# joystick-tester-smd.net
KiCad netlist of a schematic drawn in EAGLE
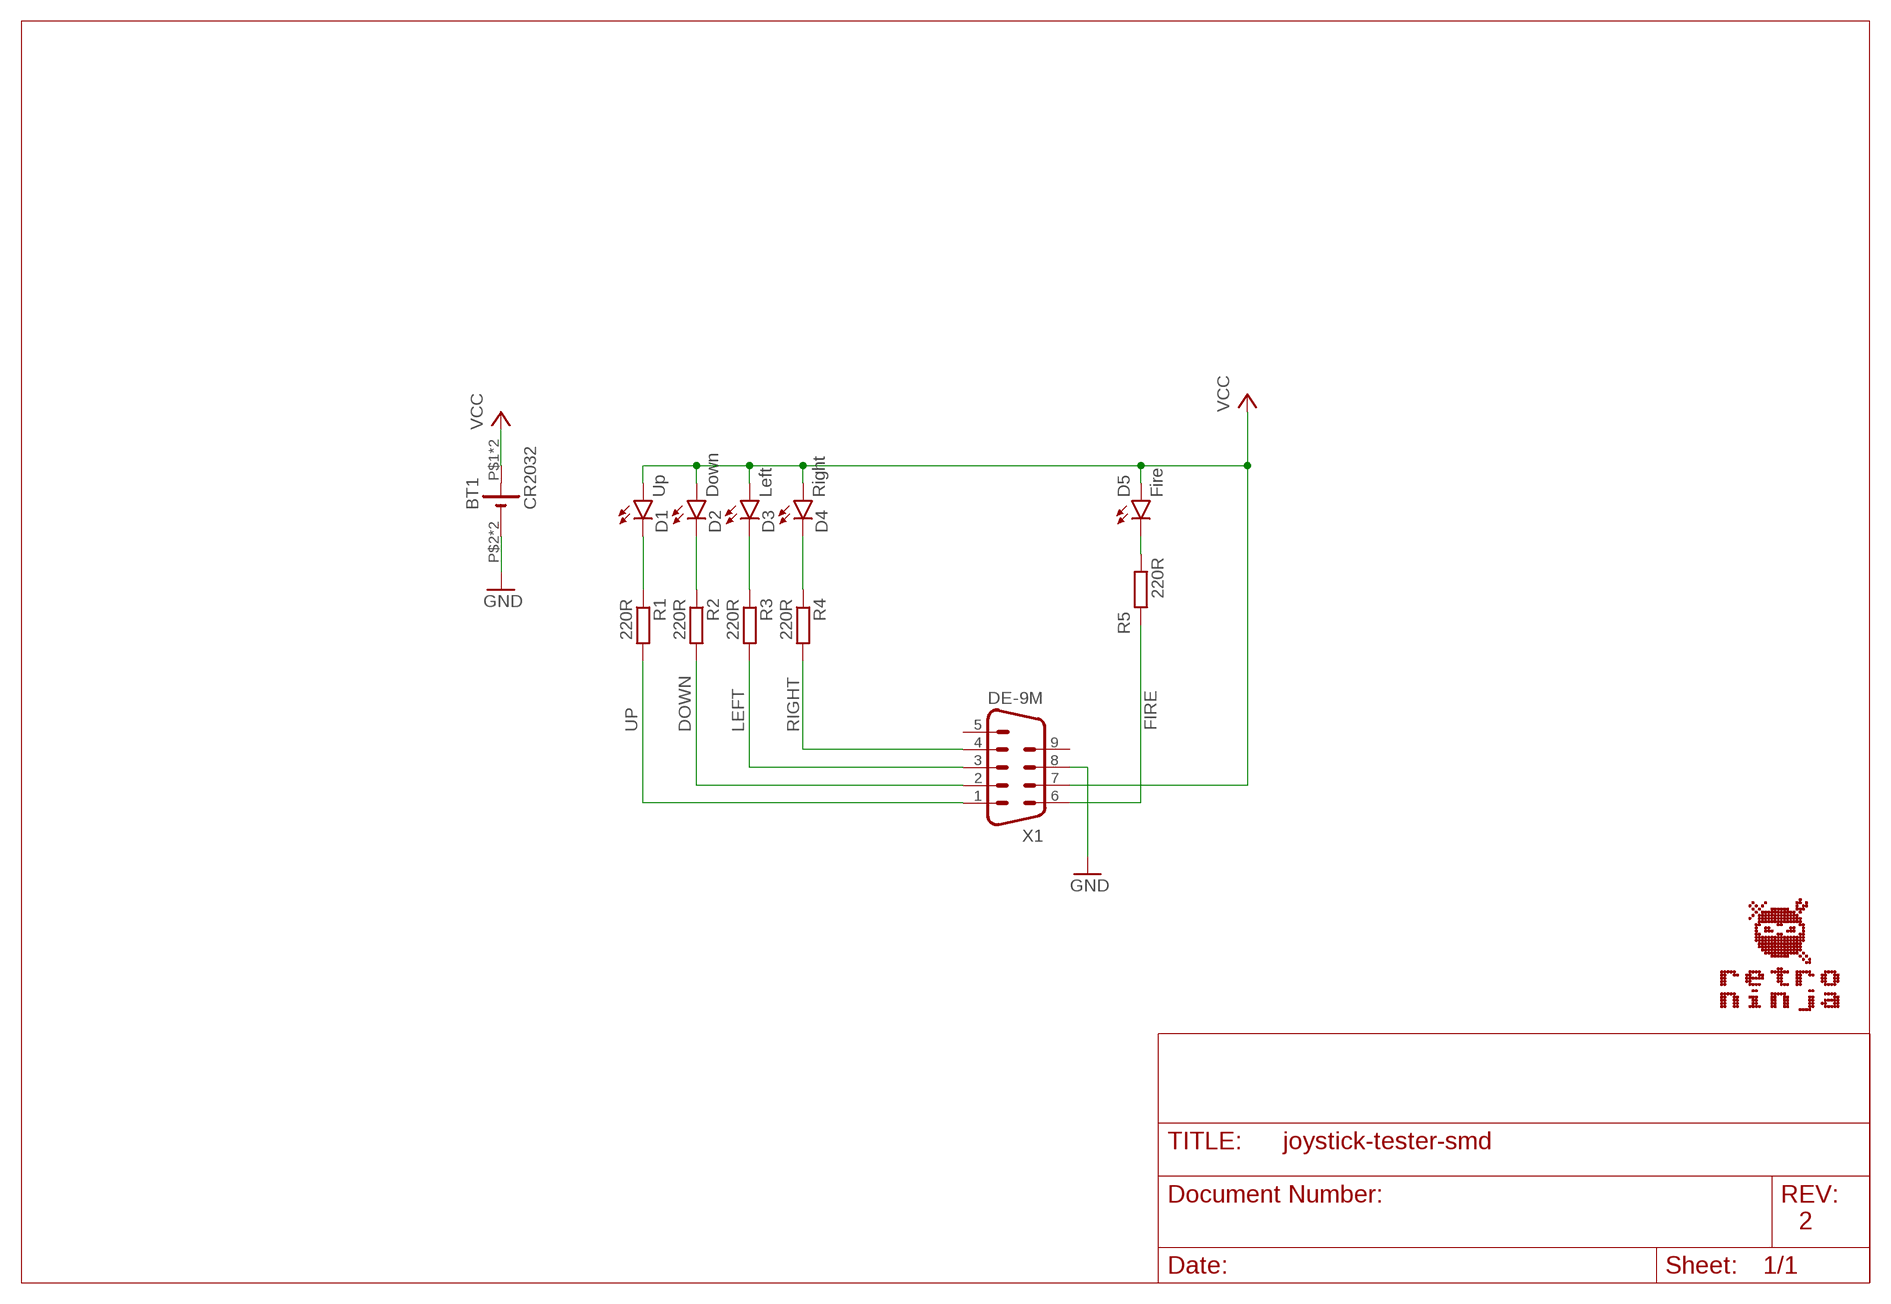
[diagram p0: schematic, sheet 1]

(export (version "E")
  (design (tool "Eeschema 10.0.6"))
  (components
    (comp (ref "BT1")
      (value "CR2032")
      (footprint "eagle-import:CR2032_2P30SMD_20MM_COMBO")
      (libsource (lib "eagle-import") (part "CR2032-COMBO-20MM-30MM_SMD"))
    )
    (comp (ref "D1")
      (value "Up")
      (footprint "eagle-import:LED-1206")
      (libsource (lib "eagle-import") (part "LED1206"))
    )
    (comp (ref "D2")
      (value "Down")
      (footprint "eagle-import:LED-1206")
      (libsource (lib "eagle-import") (part "LED1206"))
    )
    (comp (ref "D3")
      (value "Left")
      (footprint "eagle-import:LED-1206")
      (libsource (lib "eagle-import") (part "LED1206"))
    )
    (comp (ref "D4")
      (value "Right")
      (footprint "eagle-import:LED-1206")
      (libsource (lib "eagle-import") (part "LED1206"))
    )
    (comp (ref "D5")
      (value "Fire")
      (footprint "eagle-import:LED-1206")
      (libsource (lib "eagle-import") (part "LED1206"))
    )
    (comp (ref "R1")
      (value "220R")
      (footprint "eagle-import:M0805")
      (libsource (lib "eagle-import") (part "R-EU_M0805"))
    )
    (comp (ref "R2")
      (value "220R")
      (footprint "eagle-import:M0805")
      (libsource (lib "eagle-import") (part "R-EU_M0805"))
    )
    (comp (ref "R3")
      (value "220R")
      (footprint "eagle-import:M0805")
      (libsource (lib "eagle-import") (part "R-EU_M0805"))
    )
    (comp (ref "R4")
      (value "220R")
      (footprint "eagle-import:M0805")
      (libsource (lib "eagle-import") (part "R-EU_M0805"))
    )
    (comp (ref "R5")
      (value "220R")
      (footprint "eagle-import:M0805")
      (libsource (lib "eagle-import") (part "R-EU_M0805"))
    )
    (comp (ref "X1")
      (value "DE-9M")
      (footprint "eagle-import:M09D")
      (libsource (lib "eagle-import") (part "M09D"))
    )
  )
  (nets
    (net (code "1") (name "/DOWN") (class "Default")
      (node (ref "R2") (pin "2") (pinfunction "2_2") (pintype "passive"))
      (node (ref "X1") (pin "2") (pinfunction "2_2") (pintype "passive"))
    )
    (net (code "2") (name "/FIRE") (class "Default")
      (node (ref "R5") (pin "1") (pinfunction "1_1") (pintype "passive"))
      (node (ref "X1") (pin "6") (pinfunction "6_6") (pintype "passive"))
    )
    (net (code "3") (name "/LEFT") (class "Default")
      (node (ref "R3") (pin "2") (pinfunction "2_2") (pintype "passive"))
      (node (ref "X1") (pin "3") (pinfunction "3_3") (pintype "passive"))
    )
    (net (code "4") (name "/RIGHT") (class "Default")
      (node (ref "R4") (pin "2") (pinfunction "2_2") (pintype "passive"))
      (node (ref "X1") (pin "4") (pinfunction "4_4") (pintype "passive"))
    )
    (net (code "5") (name "/UP") (class "Default")
      (node (ref "R1") (pin "2") (pinfunction "2_2") (pintype "passive"))
      (node (ref "X1") (pin "1") (pinfunction "1_1") (pintype "passive"))
    )
    (net (code "6") (name "GND") (class "Default")
      (node (ref "BT1") (pin "P$2") (pinfunction "-_P$2") (pintype "passive"))
      (node (ref "BT1") (pin "P$4") (pinfunction "-_P$4") (pintype "passive"))
      (node (ref "X1") (pin "8") (pinfunction "8_8") (pintype "passive"))
    )
    (net (code "7") (name "Net-(D1-PadC)") (class "Default")
      (node (ref "D1") (pin "C") (pinfunction "C_C") (pintype "passive"))
      (node (ref "R1") (pin "1") (pinfunction "1_1") (pintype "passive"))
    )
    (net (code "8") (name "Net-(D2-PadC)") (class "Default")
      (node (ref "D2") (pin "C") (pinfunction "C_C") (pintype "passive"))
      (node (ref "R2") (pin "1") (pinfunction "1_1") (pintype "passive"))
    )
    (net (code "9") (name "Net-(D3-PadC)") (class "Default")
      (node (ref "D3") (pin "C") (pinfunction "C_C") (pintype "passive"))
      (node (ref "R3") (pin "1") (pinfunction "1_1") (pintype "passive"))
    )
    (net (code "10") (name "Net-(D4-PadC)") (class "Default")
      (node (ref "D4") (pin "C") (pinfunction "C_C") (pintype "passive"))
      (node (ref "R4") (pin "1") (pinfunction "1_1") (pintype "passive"))
    )
    (net (code "11") (name "Net-(D5-PadC)") (class "Default")
      (node (ref "D5") (pin "C") (pinfunction "C_C") (pintype "passive"))
      (node (ref "R5") (pin "2") (pinfunction "2_2") (pintype "passive"))
    )
    (net (code "12") (name "VCC") (class "Default")
      (node (ref "BT1") (pin "P$1") (pinfunction "+_P$1") (pintype "passive"))
      (node (ref "BT1") (pin "P$3") (pinfunction "+_P$3") (pintype "passive"))
      (node (ref "D1") (pin "A") (pinfunction "A_A") (pintype "passive"))
      (node (ref "D2") (pin "A") (pinfunction "A_A") (pintype "passive"))
      (node (ref "D3") (pin "A") (pinfunction "A_A") (pintype "passive"))
      (node (ref "D4") (pin "A") (pinfunction "A_A") (pintype "passive"))
      (node (ref "D5") (pin "A") (pinfunction "A_A") (pintype "passive"))
      (node (ref "X1") (pin "7") (pinfunction "7_7") (pintype "passive"))
    )
    (net (code "13") (name "unconnected-(X1-Pad5)") (class "Default")
      (node (ref "X1") (pin "5") (pinfunction "5_5") (pintype "passive"))
    )
    (net (code "14") (name "unconnected-(X1-Pad9)") (class "Default")
      (node (ref "X1") (pin "9") (pinfunction "9_9") (pintype "passive"))
    )
  )
)
